# 02_MCU.net
KiCad netlist of a schematic drawn in Altium Designer
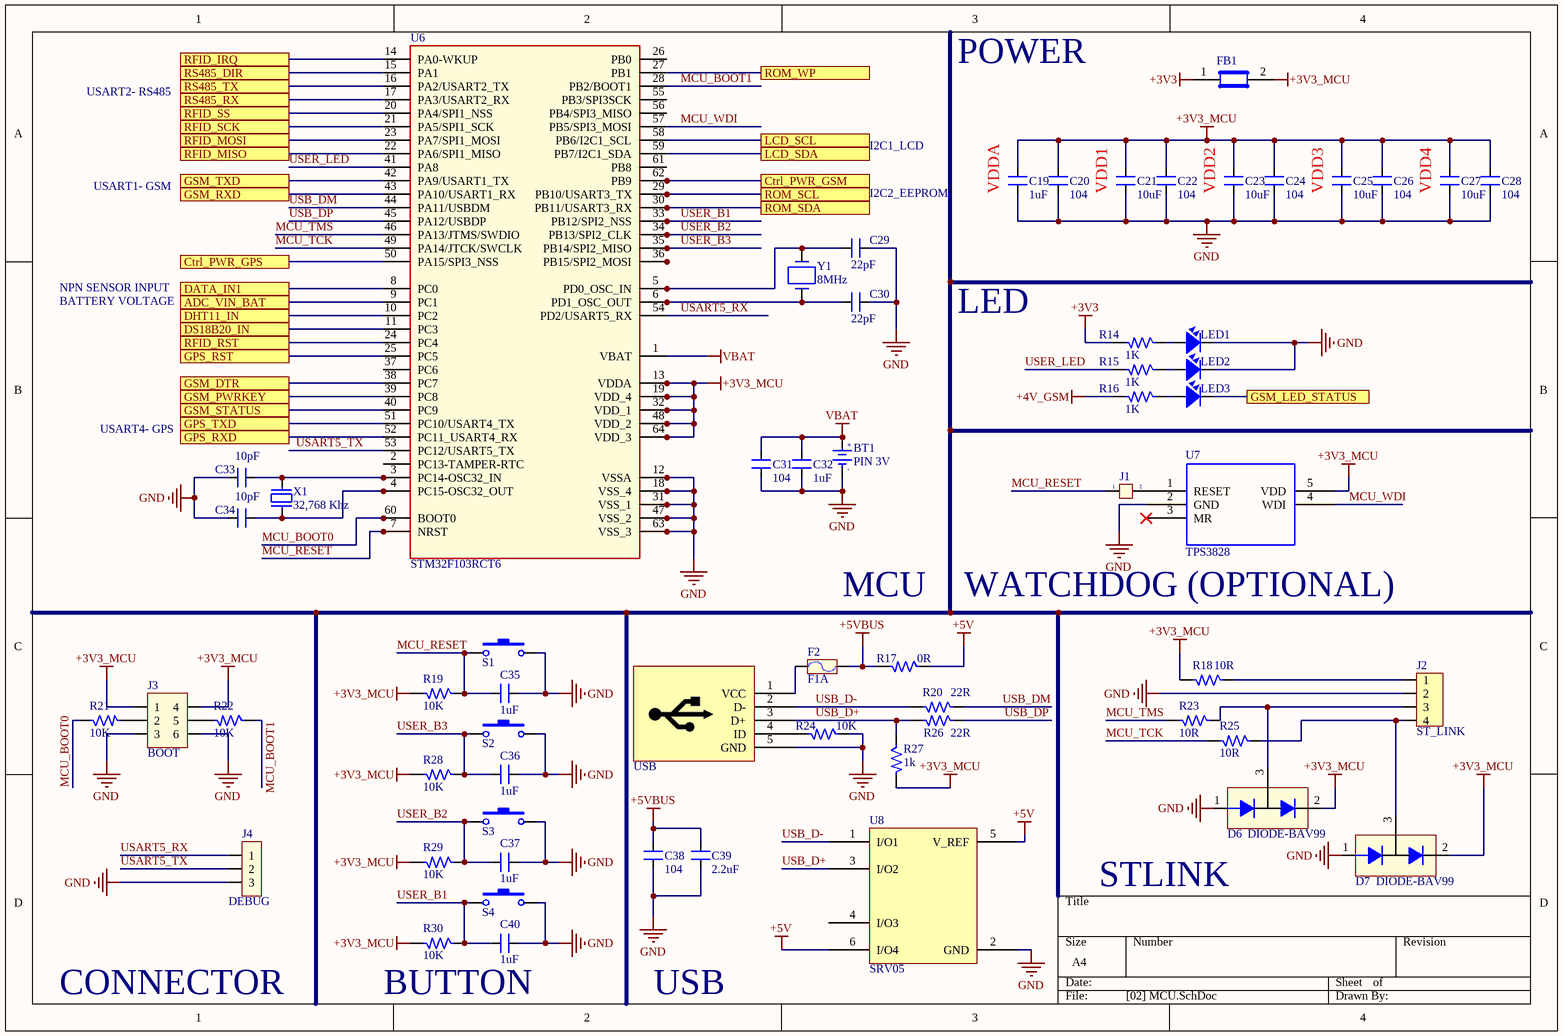
[diagram p0: [02] MCU.SchDoc]

(export (version "E")
  (design (tool "Eeschema 10.0.6"))
  (components
    (comp (ref "BT1")
      (value "PIN 3V")
      (footprint "CR1220 SMD")
      (description "Battery 3VDC")
      (libsource (lib "My Library") (part "PIN 3V"))
    )
    (comp (ref "C19")
      (value "1uF")
      (footprint "C0603 SMT")
      (description "Cap SMD")
      (libsource (lib "GPS_Traking_V1_1") (part "CM"))
    )
    (comp (ref "C20")
      (value "104")
      (footprint "C0603 SMT")
      (description "Cap SMD")
      (libsource (lib "GPS_Traking_V1_1") (part "CM"))
    )
    (comp (ref "C21")
      (value "10uF")
      (footprint "C0603 SMT")
      (description "Cap SMD")
      (libsource (lib "GPS_Traking_V1_1") (part "CM"))
    )
    (comp (ref "C22")
      (value "104")
      (footprint "C0603 SMT")
      (description "Cap SMD")
      (libsource (lib "GPS_Traking_V1_1") (part "CM"))
    )
    (comp (ref "C23")
      (value "10uF")
      (footprint "C0603 SMT")
      (description "Cap SMD")
      (libsource (lib "GPS_Traking_V1_1") (part "CM"))
    )
    (comp (ref "C24")
      (value "104")
      (footprint "C0603 SMT")
      (description "Cap SMD")
      (libsource (lib "GPS_Traking_V1_1") (part "CM"))
    )
    (comp (ref "C25")
      (value "10uF")
      (footprint "C0603 SMT")
      (description "Cap SMD")
      (libsource (lib "GPS_Traking_V1_1") (part "CM"))
    )
    (comp (ref "C26")
      (value "104")
      (footprint "C0603 SMT")
      (description "Cap SMD")
      (libsource (lib "GPS_Traking_V1_1") (part "CM"))
    )
    (comp (ref "C27")
      (value "10uF")
      (footprint "C0603 SMT")
      (description "Cap SMD")
      (libsource (lib "GPS_Traking_V1_1") (part "CM"))
    )
    (comp (ref "C28")
      (value "104")
      (footprint "C0603 SMT")
      (description "Cap SMD")
      (libsource (lib "GPS_Traking_V1_1") (part "CM"))
    )
    (comp (ref "C29")
      (value "22pF")
      (footprint "C0603 SMT")
      (description "Cap SMD")
      (libsource (lib "GPS_Traking_V1_1") (part "CM"))
    )
    (comp (ref "C30")
      (value "22pF")
      (footprint "GPS_Traking_V1_1:C0603 SMT")
      (description "Cap SMD")
      (libsource (lib "My Library") (part "CM"))
    )
    (comp (ref "C31")
      (value "104")
      (footprint "C0603 SMT")
      (description "Cap SMD")
      (libsource (lib "GPS_Traking_V1_1") (part "CM"))
    )
    (comp (ref "C32")
      (value "1uF")
      (footprint "GPS_Traking_V1_1:C0603 SMT")
      (description "Cap SMD")
      (libsource (lib "My Library") (part "CM"))
    )
    (comp (ref "C33")
      (value "10pF")
      (footprint "C0603 SMT")
      (description "Cap SMD")
      (libsource (lib "GPS_Traking_V1_1") (part "CM"))
    )
    (comp (ref "C34")
      (value "10pF")
      (footprint "C0603 SMT")
      (description "Cap SMD")
      (libsource (lib "GPS_Traking_V1_1") (part "CM"))
    )
    (comp (ref "C35")
      (value "1uF")
      (footprint "CAP_0805")
      (description "Cap SMD")
      (libsource (lib "GPS_Traking_V1_1") (part "CM"))
    )
    (comp (ref "C36")
      (value "1uF")
      (footprint "CAP_0805")
      (description "Cap SMD")
      (libsource (lib "GPS_Traking_V1_1") (part "CM"))
    )
    (comp (ref "C37")
      (value "1uF")
      (footprint "CAP_0805")
      (description "Cap SMD")
      (libsource (lib "GPS_Traking_V1_1") (part "CM"))
    )
    (comp (ref "C38")
      (value "104")
      (footprint "C0603 SMT")
      (description "Cap SMD")
      (libsource (lib "GPS_Traking_V1_1") (part "CM"))
    )
    (comp (ref "C39")
      (value "2.2uF")
      (footprint "RES-SMD-1210")
      (description "Cap SMD")
      (libsource (lib "My Library") (part "CM"))
    )
    (comp (ref "C40")
      (value "1uF")
      (footprint "CAP_0805")
      (description "Cap SMD")
      (libsource (lib "GPS_Traking_V1_1") (part "CM"))
    )
    (comp (ref "D6")
      (value "DIODE-BAV99")
      (footprint "SOT23")
      (description "ZENER, SOT23,")
      (fields
        (field (name "MANUFACTURER") "ON Semiconductor / Fairchild")
        (field (name "MANUFACTURER PART NUMBER") "BAV99")
        (field (name ".CREATOR") "LeKhaLinh")
        (field (name ".CHECKPCB") "LeKhaLinh")
        (field (name ".CHECKSCH") "LeKhaLinh")
      )
      (libsource (lib "GPS_Traking_V1_1") (part "DIODE-BAV99"))
    )
    (comp (ref "D7")
      (value "DIODE-BAV99")
      (footprint "SOT23")
      (description "ZENER, SOT23,")
      (fields
        (field (name "MANUFACTURER") "ON Semiconductor / Fairchild")
        (field (name "MANUFACTURER PART NUMBER") "BAV99")
        (field (name ".CREATOR") "LeKhaLinh")
        (field (name ".CHECKPCB") "LeKhaLinh")
        (field (name ".CHECKSCH") "LeKhaLinh")
      )
      (libsource (lib "GPS_Traking_V1_1") (part "DIODE-BAV99"))
    )
    (comp (ref "F2")
      (value "F1A")
      (footprint "RES-SMD-1812")
      (description "Fuse")
      (fields (field (name "DESIGNED BY") "VanDungEvn"))
      (libsource (lib "My Library") (part "Fuse"))
    )
    (comp (ref "FB1")
      (value "BLM21PG600SN1D")
      (footprint "GPS_Traking_V1_1:R0805")
      (description "Ferrite Bead")
      (libsource (lib "khapham") (part "Ferrite Bead"))
    )
    (comp (ref "J1")
      (value "watdog")
      (footprint "JP2")
      (description "Jumper 2")
      (libsource (lib "GPS_Traking_V1_1") (part "JP 2"))
    )
    (comp (ref "J2")
      (value "ST_LINK")
      (footprint "CON_4P")
      (description "Header IDC, 4 x 1 Pin Vertical 2.54mm Pitch (Non-Boxed, Male)")
      (fields
        (field (name "MANUFACTURER") "Würth Elektronik eiSos GmbH")
        (field (name "PARTNO") "613002143121")
        (field (name "CREATED BY") "Karrer Zheng")
      )
      (libsource (lib "My Library") (part "Header4"))
    )
    (comp (ref "J3")
      (value "BOOT")
      (footprint "JP3x2")
      (description "Connector 3x2")
      (libsource (lib "GPS_Traking_V1_1") (part "JP3x2"))
    )
    (comp (ref "J4")
      (value "DEBUG")
      (footprint "JP3")
      (description "Jumper 3")
      (libsource (lib "My Library") (part "JP3"))
    )
    (comp (ref "LED1")
      (value "LED")
      (footprint "LED-0805-Green")
      (description "LED Single colour Green and Red")
      (libsource (lib "My Library") (part "LED"))
    )
    (comp (ref "LED2")
      (value "LED")
      (footprint "LED-0805-Yellow")
      (description "LED Single colour Green and Red")
      (libsource (lib "My Library") (part "LED"))
    )
    (comp (ref "LED3")
      (value "LED")
      (footprint "LED-0805-Red")
      (description "LED Single colour Green and Red")
      (libsource (lib "My Library") (part "LED"))
    )
    (comp (ref "R14")
      (value "1K")
      (footprint "RES-SMD-0805")
      (description "Resistor SMD")
      (libsource (lib "GPS_Traking_V1_1") (part "RM"))
    )
    (comp (ref "R15")
      (value "1K")
      (footprint "RES-SMD-0805")
      (description "Resistor SMD")
      (libsource (lib "GPS_Traking_V1_1") (part "RM"))
    )
    (comp (ref "R16")
      (value "1K")
      (footprint "RES-SMD-0805")
      (description "Resistor SMD")
      (libsource (lib "GPS_Traking_V1_1") (part "RM"))
    )
    (comp (ref "R17")
      (value "0R")
      (footprint "RES-SMD-0805")
      (description "Resistor SMD")
      (libsource (lib "GPS_Traking_V1_1") (part "RM"))
    )
    (comp (ref "R18")
      (value "10R")
      (footprint "RES-SMD-0805")
      (description "Resistor SMD")
      (libsource (lib "GPS_Traking_V1_1") (part "RM"))
    )
    (comp (ref "R19")
      (value "10K")
      (footprint "RES-SMD-0805")
      (description "Resistor SMD")
      (libsource (lib "GPS_Traking_V1_1") (part "RM"))
    )
    (comp (ref "R20")
      (value "22R")
      (footprint "RES-SMD-0603")
      (description "Resistor SMD")
      (libsource (lib "GPS_Traking_V1_1") (part "RM"))
    )
    (comp (ref "R21")
      (value "10K")
      (footprint "R0603 -SMT")
      (description "Resistor SMD")
      (libsource (lib "GPS_Traking_V1_1") (part "RM"))
    )
    (comp (ref "R22")
      (value "10K")
      (footprint "R0603 -SMT")
      (description "Resistor SMD")
      (libsource (lib "GPS_Traking_V1_1") (part "RM"))
    )
    (comp (ref "R23")
      (value "10R")
      (footprint "RES-SMD-0805")
      (description "Resistor SMD")
      (libsource (lib "GPS_Traking_V1_1") (part "RM"))
    )
    (comp (ref "R24")
      (value "10K")
      (footprint "RES-SMD-0603")
      (description "Resistor SMD")
      (libsource (lib "GPS_Traking_V1_1") (part "RM"))
    )
    (comp (ref "R25")
      (value "10R")
      (footprint "RES-SMD-0805")
      (description "Resistor SMD")
      (libsource (lib "GPS_Traking_V1_1") (part "RM"))
    )
    (comp (ref "R26")
      (value "22R")
      (footprint "RES-SMD-0603")
      (description "Resistor SMD")
      (libsource (lib "GPS_Traking_V1_1") (part "RM"))
    )
    (comp (ref "R27")
      (value "1k")
      (footprint "RES-SMD-0603")
      (description "Resistor SMD")
      (libsource (lib "GPS_Traking_V1_1") (part "RM"))
    )
    (comp (ref "R28")
      (value "10K")
      (footprint "RES-SMD-0805")
      (description "Resistor SMD")
      (libsource (lib "GPS_Traking_V1_1") (part "RM"))
    )
    (comp (ref "R29")
      (value "10K")
      (footprint "RES-SMD-0805")
      (description "Resistor SMD")
      (libsource (lib "GPS_Traking_V1_1") (part "RM"))
    )
    (comp (ref "R30")
      (value "10K")
      (footprint "RES-SMD-0805")
      (description "Resistor SMD")
      (libsource (lib "GPS_Traking_V1_1") (part "RM"))
    )
    (comp (ref "S1")
      (value "SW-SMD")
      (footprint "SW-SMD")
      (description "Switch")
      (fields (field (name "PUBLISHER") "Altium Limited"))
      (libsource (lib "My Library") (part "SW-SMD"))
    )
    (comp (ref "S2")
      (value "SW-SMD")
      (footprint "BUTTON NGHIENG")
      (description "Switch")
      (fields (field (name "PUBLISHER") "Altium Limited"))
      (libsource (lib "My Library") (part "SW-SMD"))
    )
    (comp (ref "S3")
      (value "SW-SMD")
      (footprint "BUTTON NGHIENG")
      (description "Switch")
      (fields (field (name "PUBLISHER") "Altium Limited"))
      (libsource (lib "My Library") (part "SW-SMD"))
    )
    (comp (ref "S4")
      (value "SW-SMD")
      (footprint "BUTTON NGHIENG")
      (description "Switch")
      (fields (field (name "PUBLISHER") "Altium Limited"))
      (libsource (lib "My Library") (part "SW-SMD"))
    )
    (comp (ref "U6")
      (value "STM32F103RCT6")
      (footprint "LQFP-64")
      (description "MCU 32BIT 256KB FLASH 64LQFP")
      (libsource (lib "GPS_Traking_V1_1") (part "STM32F103RCT6"))
    )
    (comp (ref "U7")
      (value "TPS3828")
      (footprint "TPS3828")
      (libsource (lib "GPS_Traking_V1_1") (part "TPS3828"))
    )
    (comp (ref "U8")
      (value "SRV05")
      (footprint "SOT23-6")
      (description "TVS DIODE 5V")
      (libsource (lib "My Library") (part "SRV05"))
    )
    (comp (ref "USB") (value "USB") (footprint "USB-B-Mini") (libsource (lib "My Library") (part "USB-M")))
    (comp (ref "X1")
      (value "32,768 Khz")
      (footprint "XT32kn")
      (description "Crystal 32,768kHz for timer real")
      (libsource (lib "GPS_Traking_V1_1") (part "XT32k"))
    )
    (comp (ref "Y1")
      (value "8MHz")
      (footprint "GPS_Traking_V1_1:ABM7_v1_1_BIG")
      (description "CRYSTAL 16MHZ 18PF SMD")
      (fields
        (field (name "MANUFACTURER") "Abracon LLC")
        (field (name "MANUFACTURER PART NUMBER") "ABM7-16.000MHZ-D2Y-T")
        (field (name ".CREATOR") "MM")
        (field (name ".CHECKED PCB") "RF")
        (field (name ".CHECKED SCH") "RF")
      )
      (libsource (lib "GPS_Traking_V1_1") (part "ABM7-16.000MHZ-D2Y-T"))
    )
  )
  (nets
    (net (code "1") (name "+3V3") (class "Default")
      (node (ref "FB1") (pin "1") (pinfunction "1_1") (pintype "passive"))
      (node (ref "R14") (pin "2") (pinfunction "2_2") (pintype "passive"))
    )
    (net (code "2") (name "+3V3_MCU") (class "Default")
      (node (ref "C19") (pin "2") (pinfunction "2_2") (pintype "passive"))
      (node (ref "C20") (pin "2") (pinfunction "2_2") (pintype "passive"))
      (node (ref "C21") (pin "2") (pinfunction "2_2") (pintype "passive"))
      (node (ref "C22") (pin "2") (pinfunction "2_2") (pintype "passive"))
      (node (ref "C23") (pin "2") (pinfunction "2_2") (pintype "passive"))
      (node (ref "C24") (pin "2") (pinfunction "2_2") (pintype "passive"))
      (node (ref "C25") (pin "2") (pinfunction "2_2") (pintype "passive"))
      (node (ref "C26") (pin "2") (pinfunction "2_2") (pintype "passive"))
      (node (ref "C27") (pin "2") (pinfunction "2_2") (pintype "passive"))
      (node (ref "C28") (pin "2") (pinfunction "2_2") (pintype "passive"))
      (node (ref "D6") (pin "2") (pinfunction "2_2") (pintype "passive"))
      (node (ref "D7") (pin "2") (pinfunction "2_2") (pintype "passive"))
      (node (ref "FB1") (pin "2") (pinfunction "2_2") (pintype "passive"))
      (node (ref "J3") (pin "1") (pinfunction "1_1") (pintype "passive"))
      (node (ref "J3") (pin "4") (pinfunction "4_4") (pintype "passive"))
      (node (ref "R18") (pin "2") (pinfunction "2_2") (pintype "passive"))
      (node (ref "R19") (pin "2") (pinfunction "2_2") (pintype "passive"))
      (node (ref "R27") (pin "2") (pinfunction "2_2") (pintype "passive"))
      (node (ref "R28") (pin "2") (pinfunction "2_2") (pintype "passive"))
      (node (ref "R29") (pin "2") (pinfunction "2_2") (pintype "passive"))
      (node (ref "R30") (pin "2") (pinfunction "2_2") (pintype "passive"))
      (node (ref "U6") (pin "13") (pinfunction "VDDA_13") (pintype "passive"))
      (node (ref "U6") (pin "19") (pinfunction "VDD_4_19") (pintype "passive"))
      (node (ref "U6") (pin "32") (pinfunction "VDD_1_32") (pintype "passive"))
      (node (ref "U6") (pin "48") (pinfunction "VDD_2_48") (pintype "passive"))
      (node (ref "U6") (pin "64") (pinfunction "VDD_3_64") (pintype "passive"))
      (node (ref "U7") (pin "5") (pinfunction "VDD_5") (pintype "power_in"))
    )
    (net (code "3") (name "+4V_GSM") (class "Default")
      (node (ref "R16") (pin "2") (pinfunction "2_2") (pintype "passive"))
    )
    (net (code "4") (name "+5V") (class "Default")
      (node (ref "R17") (pin "1") (pinfunction "1_1") (pintype "passive"))
      (node (ref "U8") (pin "5") (pinfunction "V_REF_5") (pintype "passive"))
      (node (ref "U8") (pin "6") (pinfunction "I/O4_6") (pintype "passive"))
    )
    (net (code "5") (name "+5VBUS") (class "Default")
      (node (ref "C38") (pin "2") (pinfunction "2_2") (pintype "passive"))
      (node (ref "C39") (pin "2") (pinfunction "2_2") (pintype "passive"))
      (node (ref "F2") (pin "2") (pinfunction "2_2") (pintype "passive"))
      (node (ref "R17") (pin "2") (pinfunction "2_2") (pintype "passive"))
    )
    (net (code "6") (name "/ADC_VIN_BAT") (class "Default")
      (node (ref "U6") (pin "9") (pinfunction "PC1_9") (pintype "passive"))
    )
    (net (code "7") (name "/Ctrl_PWR_GPS") (class "Default")
      (node (ref "U6") (pin "50") (pinfunction "PA15/SPI3_NSS_50") (pintype "passive"))
    )
    (net (code "8") (name "/Ctrl_PWR_GSM") (class "Default")
      (node (ref "U6") (pin "62") (pinfunction "PB9_62") (pintype "passive"))
    )
    (net (code "9") (name "/DATA_IN1") (class "Default")
      (node (ref "U6") (pin "8") (pinfunction "PC0_8") (pintype "passive"))
    )
    (net (code "10") (name "/DHT11_IN") (class "Default")
      (node (ref "U6") (pin "10") (pinfunction "PC2_10") (pintype "passive"))
    )
    (net (code "11") (name "/DS18B20_IN") (class "Default")
      (node (ref "U6") (pin "11") (pinfunction "PC3_11") (pintype "passive"))
    )
    (net (code "12") (name "/GPS_RST") (class "Default")
      (node (ref "U6") (pin "25") (pinfunction "PC5_25") (pintype "passive"))
    )
    (net (code "13") (name "/GPS_RXD") (class "Default")
      (node (ref "U6") (pin "52") (pinfunction "PC11_USART4_RX_52") (pintype "passive"))
    )
    (net (code "14") (name "/GPS_TXD") (class "Default")
      (node (ref "U6") (pin "51") (pinfunction "PC10/USART4_TX_51") (pintype "passive"))
    )
    (net (code "15") (name "/GSM_DTR") (class "Default")
      (node (ref "U6") (pin "38") (pinfunction "PC7_38") (pintype "passive"))
    )
    (net (code "16") (name "/GSM_LED_STATUS") (class "Default")
      (node (ref "LED3") (pin "2") (pinfunction "2_2") (pintype "passive"))
    )
    (net (code "17") (name "/GSM_PWRKEY") (class "Default")
      (node (ref "U6") (pin "39") (pinfunction "PC8_39") (pintype "passive"))
    )
    (net (code "18") (name "/GSM_RXD") (class "Default")
      (node (ref "U6") (pin "43") (pinfunction "PA10/USART1_RX_43") (pintype "passive"))
    )
    (net (code "19") (name "/GSM_STATUS") (class "Default")
      (node (ref "U6") (pin "40") (pinfunction "PC9_40") (pintype "passive"))
    )
    (net (code "20") (name "/GSM_TXD") (class "Default")
      (node (ref "U6") (pin "42") (pinfunction "PA9/USART1_TX_42") (pintype "passive"))
    )
    (net (code "21") (name "/LCD_SCL") (class "Default")
      (node (ref "U6") (pin "58") (pinfunction "PB6/I2C1_SCL_58") (pintype "passive"))
    )
    (net (code "22") (name "/LCD_SDA") (class "Default")
      (node (ref "U6") (pin "59") (pinfunction "PB7/I2C1_SDA_59") (pintype "passive"))
    )
    (net (code "23") (name "/MCU_BOOT0") (class "Default")
      (node (ref "R21") (pin "1") (pinfunction "1_1") (pintype "passive"))
      (node (ref "U6") (pin "60") (pinfunction "BOOT0_60") (pintype "passive"))
    )
    (net (code "24") (name "/MCU_BOOT1") (class "Default")
      (node (ref "R22") (pin "1") (pinfunction "1_1") (pintype "passive"))
      (node (ref "U6") (pin "28") (pinfunction "PB2/BOOT1_28") (pintype "passive"))
    )
    (net (code "25") (name "/MCU_RESET") (class "Default")
      (node (ref "C35") (pin "1") (pinfunction "1_1") (pintype "passive"))
      (node (ref "J1") (pin "1") (pinfunction "1_1") (pintype "passive"))
      (node (ref "R19") (pin "1") (pinfunction "1_1") (pintype "passive"))
      (node (ref "S1") (pin "1") (pinfunction "1_1") (pintype "passive"))
      (node (ref "U6") (pin "7") (pinfunction "NRST_7") (pintype "passive"))
    )
    (net (code "26") (name "/MCU_TCK") (class "Default")
      (node (ref "R25") (pin "2") (pinfunction "2_2") (pintype "passive"))
      (node (ref "U6") (pin "49") (pinfunction "PA14/JTCK/SWCLK_49") (pintype "passive"))
    )
    (net (code "27") (name "/MCU_TMS") (class "Default")
      (node (ref "R23") (pin "2") (pinfunction "2_2") (pintype "passive"))
      (node (ref "U6") (pin "46") (pinfunction "PA13/JTMS/SWDIO_46") (pintype "passive"))
    )
    (net (code "28") (name "/MCU_WDI") (class "Default")
      (node (ref "U6") (pin "57") (pinfunction "PB5/SPI3_MOSI_57") (pintype "passive"))
      (node (ref "U7") (pin "4") (pinfunction "WDI_4") (pintype "passive"))
    )
    (net (code "29") (name "/RFID_IRQ") (class "Default")
      (node (ref "U6") (pin "14") (pinfunction "PA0-WKUP_14") (pintype "passive"))
    )
    (net (code "30") (name "/RFID_MISO") (class "Default")
      (node (ref "U6") (pin "22") (pinfunction "PA6/SPI1_MISO_22") (pintype "passive"))
    )
    (net (code "31") (name "/RFID_MOSI") (class "Default")
      (node (ref "U6") (pin "23") (pinfunction "PA7/SPI1_MOSI_23") (pintype "passive"))
    )
    (net (code "32") (name "/RFID_RST") (class "Default")
      (node (ref "U6") (pin "24") (pinfunction "PC4_24") (pintype "passive"))
    )
    (net (code "33") (name "/RFID_SCK") (class "Default")
      (node (ref "U6") (pin "21") (pinfunction "PA5/SPI1_SCK_21") (pintype "passive"))
    )
    (net (code "34") (name "/RFID_SS") (class "Default")
      (node (ref "U6") (pin "20") (pinfunction "PA4/SPI1_NSS_20") (pintype "passive"))
    )
    (net (code "35") (name "/ROM_SCL") (class "Default")
      (node (ref "U6") (pin "29") (pinfunction "PB10/USART3_TX_29") (pintype "passive"))
    )
    (net (code "36") (name "/ROM_SDA") (class "Default")
      (node (ref "U6") (pin "30") (pinfunction "PB11/USART3_RX_30") (pintype "passive"))
    )
    (net (code "37") (name "/ROM_WP") (class "Default")
      (node (ref "U6") (pin "27") (pinfunction "PB1_27") (pintype "passive"))
    )
    (net (code "38") (name "/RS485_DIR") (class "Default")
      (node (ref "U6") (pin "15") (pinfunction "PA1_15") (pintype "passive"))
    )
    (net (code "39") (name "/RS485_RX") (class "Default")
      (node (ref "U6") (pin "17") (pinfunction "PA3/USART2_RX_17") (pintype "passive"))
    )
    (net (code "40") (name "/RS485_TX") (class "Default")
      (node (ref "U6") (pin "16") (pinfunction "PA2/USART2_TX_16") (pintype "passive"))
    )
    (net (code "41") (name "/USART5_RX") (class "Default")
      (node (ref "J4") (pin "1") (pinfunction "1_1") (pintype "passive"))
      (node (ref "U6") (pin "54") (pinfunction "PD2/USART5_RX_54") (pintype "passive"))
    )
    (net (code "42") (name "/USART5_TX") (class "Default")
      (node (ref "J4") (pin "2") (pinfunction "2_2") (pintype "passive"))
      (node (ref "U6") (pin "53") (pinfunction "PC12/USART5_TX_53") (pintype "passive"))
    )
    (net (code "43") (name "/USB_D+") (class "Default")
      (node (ref "R26") (pin "2") (pinfunction "2_2") (pintype "passive"))
      (node (ref "R27") (pin "1") (pinfunction "1_1") (pintype "passive"))
      (node (ref "U8") (pin "3") (pinfunction "I/O2_3") (pintype "passive"))
      (node (ref "USB") (pin "3") (pinfunction "D+_3") (pintype "passive"))
    )
    (net (code "44") (name "/USB_D-") (class "Default")
      (node (ref "R20") (pin "2") (pinfunction "2_2") (pintype "passive"))
      (node (ref "U8") (pin "1") (pinfunction "I/O1_1") (pintype "passive"))
      (node (ref "USB") (pin "2") (pinfunction "D-_2") (pintype "passive"))
    )
    (net (code "45") (name "/USB_DM") (class "Default")
      (node (ref "R20") (pin "1") (pinfunction "1_1") (pintype "passive"))
      (node (ref "U6") (pin "44") (pinfunction "PA11/USBDM_44") (pintype "passive"))
    )
    (net (code "46") (name "/USB_DP") (class "Default")
      (node (ref "R26") (pin "1") (pinfunction "1_1") (pintype "passive"))
      (node (ref "U6") (pin "45") (pinfunction "PA12/USBDP_45") (pintype "passive"))
    )
    (net (code "47") (name "/USER_B1") (class "Default")
      (node (ref "C40") (pin "1") (pinfunction "1_1") (pintype "passive"))
      (node (ref "R30") (pin "1") (pinfunction "1_1") (pintype "passive"))
      (node (ref "S4") (pin "1") (pinfunction "1_1") (pintype "passive"))
      (node (ref "U6") (pin "33") (pinfunction "PB12/SPI2_NSS_33") (pintype "passive"))
    )
    (net (code "48") (name "/USER_B2") (class "Default")
      (node (ref "C37") (pin "1") (pinfunction "1_1") (pintype "passive"))
      (node (ref "R29") (pin "1") (pinfunction "1_1") (pintype "passive"))
      (node (ref "S3") (pin "1") (pinfunction "1_1") (pintype "passive"))
      (node (ref "U6") (pin "34") (pinfunction "PB13/SPI2_CLK_34") (pintype "passive"))
    )
    (net (code "49") (name "/USER_B3") (class "Default")
      (node (ref "C36") (pin "1") (pinfunction "1_1") (pintype "passive"))
      (node (ref "R28") (pin "1") (pinfunction "1_1") (pintype "passive"))
      (node (ref "S2") (pin "1") (pinfunction "1_1") (pintype "passive"))
      (node (ref "U6") (pin "35") (pinfunction "PB14/SPI2_MISO_35") (pintype "passive"))
    )
    (net (code "50") (name "/USER_LED") (class "Default")
      (node (ref "R15") (pin "2") (pinfunction "2_2") (pintype "passive"))
      (node (ref "U6") (pin "41") (pinfunction "PA8_41") (pintype "passive"))
    )
    (net (code "51") (name "GND") (class "Default")
      (node (ref "BT1") (pin "2") (pinfunction "GND_2") (pintype "passive"))
      (node (ref "C19") (pin "1") (pinfunction "1_1") (pintype "passive"))
      (node (ref "C20") (pin "1") (pinfunction "1_1") (pintype "passive"))
      (node (ref "C21") (pin "1") (pinfunction "1_1") (pintype "passive"))
      (node (ref "C22") (pin "1") (pinfunction "1_1") (pintype "passive"))
      (node (ref "C23") (pin "1") (pinfunction "1_1") (pintype "passive"))
      (node (ref "C24") (pin "1") (pinfunction "1_1") (pintype "passive"))
      (node (ref "C25") (pin "1") (pinfunction "1_1") (pintype "passive"))
      (node (ref "C26") (pin "1") (pinfunction "1_1") (pintype "passive"))
      (node (ref "C27") (pin "1") (pinfunction "1_1") (pintype "passive"))
      (node (ref "C28") (pin "1") (pinfunction "1_1") (pintype "passive"))
      (node (ref "C29") (pin "2") (pinfunction "2_2") (pintype "passive"))
      (node (ref "C30") (pin "2") (pinfunction "2_2") (pintype "passive"))
      (node (ref "C31") (pin "1") (pinfunction "1_1") (pintype "passive"))
      (node (ref "C32") (pin "1") (pinfunction "1_1") (pintype "passive"))
      (node (ref "C33") (pin "2") (pinfunction "2_2") (pintype "passive"))
      (node (ref "C34") (pin "2") (pinfunction "2_2") (pintype "passive"))
      (node (ref "C35") (pin "2") (pinfunction "2_2") (pintype "passive"))
      (node (ref "C36") (pin "2") (pinfunction "2_2") (pintype "passive"))
      (node (ref "C37") (pin "2") (pinfunction "2_2") (pintype "passive"))
      (node (ref "C38") (pin "1") (pinfunction "1_1") (pintype "passive"))
      (node (ref "C39") (pin "1") (pinfunction "1_1") (pintype "passive"))
      (node (ref "C40") (pin "2") (pinfunction "2_2") (pintype "passive"))
      (node (ref "D6") (pin "1") (pinfunction "1_1") (pintype "passive"))
      (node (ref "D7") (pin "1") (pinfunction "1_1") (pintype "passive"))
      (node (ref "J2") (pin "2") (pinfunction "2_2") (pintype "passive"))
      (node (ref "J3") (pin "3") (pinfunction "3_3") (pintype "passive"))
      (node (ref "J3") (pin "6") (pinfunction "6_6") (pintype "passive"))
      (node (ref "J4") (pin "3") (pinfunction "3_3") (pintype "passive"))
      (node (ref "LED1") (pin "2") (pinfunction "2_2") (pintype "passive"))
      (node (ref "LED2") (pin "2") (pinfunction "2_2") (pintype "passive"))
      (node (ref "R24") (pin "1") (pinfunction "1_1") (pintype "passive"))
      (node (ref "S1") (pin "2") (pinfunction "2_2") (pintype "passive"))
      (node (ref "S2") (pin "2") (pinfunction "2_2") (pintype "passive"))
      (node (ref "S3") (pin "2") (pinfunction "2_2") (pintype "passive"))
      (node (ref "S4") (pin "2") (pinfunction "2_2") (pintype "passive"))
      (node (ref "U6") (pin "12") (pinfunction "VSSA_12") (pintype "passive"))
      (node (ref "U6") (pin "18") (pinfunction "VSS_4_18") (pintype "passive"))
      (node (ref "U6") (pin "31") (pinfunction "VSS_1_31") (pintype "passive"))
      (node (ref "U6") (pin "47") (pinfunction "VSS_2_47") (pintype "passive"))
      (node (ref "U6") (pin "63") (pinfunction "VSS_3_63") (pintype "passive"))
      (node (ref "U7") (pin "2") (pinfunction "GND_2") (pintype "power_in"))
      (node (ref "U8") (pin "2") (pinfunction "GND_2") (pintype "passive"))
      (node (ref "USB") (pin "5") (pinfunction "GND_5") (pintype "passive"))
    )
    (net (code "52") (name "Net-(D6-Pad3)") (class "Default")
      (node (ref "D6") (pin "3") (pinfunction "3_3") (pintype "passive"))
      (node (ref "J2") (pin "3") (pinfunction "3_3") (pintype "passive"))
      (node (ref "R23") (pin "1") (pinfunction "1_1") (pintype "passive"))
    )
    (net (code "53") (name "Net-(D7-Pad3)") (class "Default")
      (node (ref "D7") (pin "3") (pinfunction "3_3") (pintype "passive"))
      (node (ref "J2") (pin "4") (pinfunction "4_4") (pintype "passive"))
      (node (ref "R25") (pin "1") (pinfunction "1_1") (pintype "passive"))
    )
    (net (code "54") (name "Net-(J2-Pad1)") (class "Default")
      (node (ref "J2") (pin "1") (pinfunction "1_1") (pintype "passive"))
      (node (ref "R18") (pin "1") (pinfunction "1_1") (pintype "passive"))
    )
    (net (code "55") (name "Net-(J3-Pad2)") (class "Default")
      (node (ref "J3") (pin "2") (pinfunction "2_2") (pintype "passive"))
      (node (ref "R21") (pin "2") (pinfunction "2_2") (pintype "passive"))
    )
    (net (code "56") (name "Net-(J3-Pad5)") (class "Default")
      (node (ref "J3") (pin "5") (pinfunction "5_5") (pintype "passive"))
      (node (ref "R22") (pin "2") (pinfunction "2_2") (pintype "passive"))
    )
    (net (code "57") (name "Net-(LED1-Pad1)") (class "Default")
      (node (ref "LED1") (pin "1") (pinfunction "1_1") (pintype "passive"))
      (node (ref "R14") (pin "1") (pinfunction "1_1") (pintype "passive"))
    )
    (net (code "58") (name "Net-(LED2-Pad1)") (class "Default")
      (node (ref "LED2") (pin "1") (pinfunction "1_1") (pintype "passive"))
      (node (ref "R15") (pin "1") (pinfunction "1_1") (pintype "passive"))
    )
    (net (code "59") (name "Net-(LED3-Pad1)") (class "Default")
      (node (ref "LED3") (pin "1") (pinfunction "1_1") (pintype "passive"))
      (node (ref "R16") (pin "1") (pinfunction "1_1") (pintype "passive"))
    )
    (net (code "60") (name "Net-(U6-PC14-OSC32_IN)") (class "Default")
      (node (ref "C33") (pin "1") (pinfunction "1_1") (pintype "passive"))
      (node (ref "U6") (pin "3") (pinfunction "PC14-OSC32_IN_3") (pintype "passive"))
      (node (ref "X1") (pin "1") (pinfunction "1_1") (pintype "passive"))
    )
    (net (code "61") (name "Net-(U6-PC15-OSC32_OUT)") (class "Default")
      (node (ref "C34") (pin "1") (pinfunction "1_1") (pintype "passive"))
      (node (ref "U6") (pin "4") (pinfunction "PC15-OSC32_OUT_4") (pintype "passive"))
      (node (ref "X1") (pin "2") (pinfunction "2_2") (pintype "passive"))
    )
    (net (code "62") (name "Net-(U6-PD0_OSC_IN)") (class "Default")
      (node (ref "C29") (pin "1") (pinfunction "1_1") (pintype "passive"))
      (node (ref "U6") (pin "5") (pinfunction "PD0_OSC_IN_5") (pintype "passive"))
      (node (ref "Y1") (pin "2") (pinfunction "2_2") (pintype "passive"))
    )
    (net (code "63") (name "Net-(U6-PD1_OSC_OUT)") (class "Default")
      (node (ref "C30") (pin "1") (pinfunction "1_1") (pintype "passive"))
      (node (ref "U6") (pin "6") (pinfunction "PD1_OSC_OUT_6") (pintype "passive"))
      (node (ref "Y1") (pin "1") (pinfunction "1_1") (pintype "passive"))
    )
    (net (code "64") (name "Net-(U7-RESET)") (class "Default")
      (node (ref "J1") (pin "2") (pinfunction "2_2") (pintype "passive"))
      (node (ref "U7") (pin "1") (pinfunction "RESET_1") (pintype "passive"))
    )
    (net (code "65") (name "Net-(USB-ID)") (class "Default")
      (node (ref "R24") (pin "2") (pinfunction "2_2") (pintype "passive"))
      (node (ref "USB") (pin "4") (pinfunction "ID_4") (pintype "passive"))
    )
    (net (code "66") (name "Net-(USB-VCC)") (class "Default")
      (node (ref "F2") (pin "1") (pinfunction "1_1") (pintype "passive"))
      (node (ref "USB") (pin "1") (pinfunction "VCC_1") (pintype "passive"))
    )
    (net (code "67") (name "VBAT") (class "Default")
      (node (ref "BT1") (pin "1") (pinfunction "+3V_1") (pintype "passive"))
      (node (ref "C31") (pin "2") (pinfunction "2_2") (pintype "passive"))
      (node (ref "C32") (pin "2") (pinfunction "2_2") (pintype "passive"))
      (node (ref "U6") (pin "1") (pinfunction "VBAT_1") (pintype "passive"))
    )
    (net (code "68") (name "unconnected-(U6-PB0-Pad26)") (class "Default")
      (node (ref "U6") (pin "26") (pinfunction "PB0_26") (pintype "passive"))
    )
    (net (code "69") (name "unconnected-(U6-PB3{slash}SPI3SCK-Pad55)") (class "Default")
      (node (ref "U6") (pin "55") (pinfunction "PB3/SPI3SCK_55") (pintype "passive"))
    )
    (net (code "70") (name "unconnected-(U6-PB4{slash}SPI3_MISO-Pad56)") (class "Default")
      (node (ref "U6") (pin "56") (pinfunction "PB4/SPI3_MISO_56") (pintype "passive"))
    )
    (net (code "71") (name "unconnected-(U6-PB8-Pad61)") (class "Default")
      (node (ref "U6") (pin "61") (pinfunction "PB8_61") (pintype "passive"))
    )
    (net (code "72") (name "unconnected-(U6-PB15{slash}SPI2_MOSI-Pad36)") (class "Default")
      (node (ref "U6") (pin "36") (pinfunction "PB15/SPI2_MOSI_36") (pintype "passive"))
    )
    (net (code "73") (name "unconnected-(U6-PC6-Pad37)") (class "Default")
      (node (ref "U6") (pin "37") (pinfunction "PC6_37") (pintype "passive"))
    )
    (net (code "74") (name "unconnected-(U6-PC13-TAMPER-RTC-Pad2)") (class "Default")
      (node (ref "U6") (pin "2") (pinfunction "PC13-TAMPER-RTC_2") (pintype "passive"))
    )
    (net (code "75") (name "unconnected-(U7-MR-Pad3)") (class "Default")
      (node (ref "U7") (pin "3") (pinfunction "MR_3") (pintype "passive+no_connect"))
    )
    (net (code "76") (name "unconnected-(U8-I{slash}O3-Pad4)") (class "Default")
      (node (ref "U8") (pin "4") (pinfunction "I/O3_4") (pintype "passive"))
    )
  )
)
